# LPF_Block.net
KiCad netlist of a schematic drawn in Altium Designer
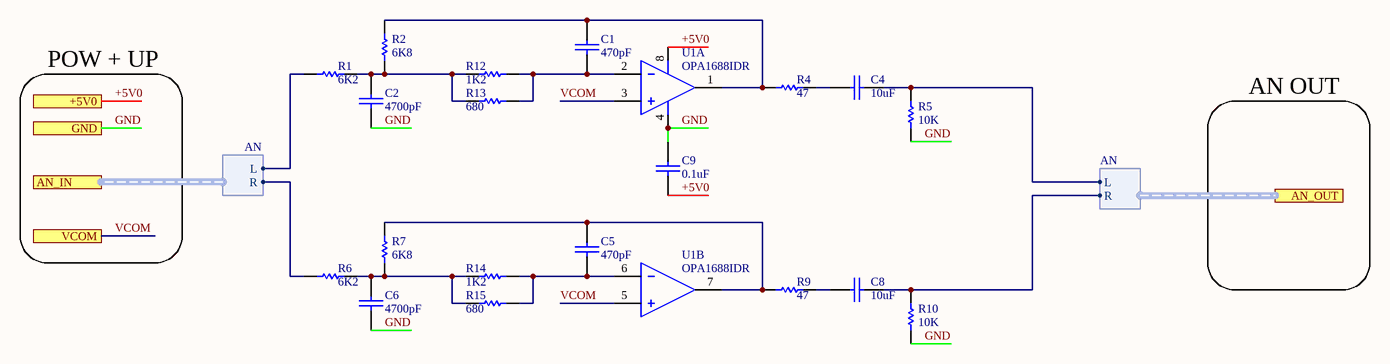
[diagram p0: LPF_Block.SchDoc]

(export (version "E")
  (design (tool "Eeschema 10.0.6"))
  (components
    (comp (ref "C1")
      (value "470pF")
      (footprint "0402-CAP-TDK")
      (fields (field (name "JLCPART") "C1537"))
      (libsource (lib "LIB2022 - Passives") (part "CAP-SMD"))
    )
    (comp (ref "C2")
      (value "4700pF")
      (footprint "0402-CAP-TDK")
      (fields (field (name "JLCPART") "C1538"))
      (libsource (lib "LIB2022 - Passives") (part "CAP-SMD"))
    )
    (comp (ref "C4")
      (value "10uF")
      (footprint "0603-CAP-TDK")
      (fields (field (name "JLCPART") "C96446"))
      (libsource (lib "LIB2022 - Passives") (part "CAP-SMD"))
    )
    (comp (ref "C5")
      (value "470pF")
      (footprint "0402-CAP-TDK")
      (fields (field (name "JLCPART") "C1537"))
      (libsource (lib "LIB2022 - Passives") (part "CAP-SMD"))
    )
    (comp (ref "C6")
      (value "4700pF")
      (footprint "0402-CAP-TDK")
      (fields (field (name "JLCPART") "C1538"))
      (libsource (lib "LIB2022 - Passives") (part "CAP-SMD"))
    )
    (comp (ref "C8")
      (value "10uF")
      (footprint "0603-CAP-TDK")
      (fields (field (name "JLCPART") "C96446"))
      (libsource (lib "LIB2022 - Passives") (part "CAP-SMD"))
    )
    (comp (ref "C9")
      (value "0.1uF")
      (footprint "0402-CAP-TDK")
      (fields (field (name "JLCPART") "C307331"))
      (libsource (lib "LIB2022 - Passives") (part "CAP-SMD"))
    )
    (comp (ref "R1")
      (value "6K2")
      (footprint "0603-RES-PANASONIC")
      (fields (field (name "JLCPART") "C4260"))
      (libsource (lib "LIB2022 - Passives") (part "RES-SMD"))
    )
    (comp (ref "R2")
      (value "6K8")
      (footprint "0402-RES-PANASONIC")
      (fields (field (name "JLCPART") "C25917"))
      (libsource (lib "LIB2022 - Passives") (part "RES-SMD"))
    )
    (comp (ref "R4")
      (value "47")
      (footprint "0402-RES-PANASONIC")
      (fields (field (name "JLCPART") "C25118"))
      (libsource (lib "LIB2022 - Passives") (part "RES-SMD"))
    )
    (comp (ref "R5")
      (value "10K")
      (footprint "0402-RES-PANASONIC")
      (fields (field (name "JLCPART") "C25744"))
      (libsource (lib "LIB2022 - Passives") (part "RES-SMD"))
    )
    (comp (ref "R6")
      (value "6K2")
      (footprint "0603-RES-PANASONIC")
      (fields (field (name "JLCPART") "C4260"))
      (libsource (lib "LIB2022 - Passives") (part "RES-SMD"))
    )
    (comp (ref "R7")
      (value "6K8")
      (footprint "0402-RES-PANASONIC")
      (fields (field (name "JLCPART") "C25917"))
      (libsource (lib "LIB2022 - Passives") (part "RES-SMD"))
    )
    (comp (ref "R9")
      (value "47")
      (footprint "0402-RES-PANASONIC")
      (fields (field (name "JLCPART") "C25118"))
      (libsource (lib "LIB2022 - Passives") (part "RES-SMD"))
    )
    (comp (ref "R10")
      (value "10K")
      (footprint "0402-RES-PANASONIC")
      (fields (field (name "JLCPART") "C25744"))
      (libsource (lib "LIB2022 - Passives") (part "RES-SMD"))
    )
    (comp (ref "R12")
      (value "1K2")
      (footprint "0402-RES-PANASONIC")
      (fields (field (name "JLCPART") "C25862"))
      (libsource (lib "LIB2022 - Passives") (part "RES-SMD"))
    )
    (comp (ref "R13")
      (value "680")
      (footprint "0402-RES-PANASONIC")
      (fields (field (name "JLCPART") "C25130"))
      (libsource (lib "LIB2022 - Passives") (part "RES-SMD"))
    )
    (comp (ref "R14")
      (value "1K2")
      (footprint "0402-RES-PANASONIC")
      (fields (field (name "JLCPART") "C25862"))
      (libsource (lib "LIB2022 - Passives") (part "RES-SMD"))
    )
    (comp (ref "R15")
      (value "680")
      (footprint "0402-RES-PANASONIC")
      (fields (field (name "JLCPART") "C25130"))
      (libsource (lib "LIB2022 - Passives") (part "RES-SMD"))
    )
    (comp (ref "U1")
      (value "OPA1688IDR")
      (footprint "TI-SOIC-8")
      (description "Rail-To-Rail Amplifier 2 Circuit - 8-SOIC")
      (fields (field (name "JLCPART") "C206212"))
      (libsource (lib "LIB2022 - ICs") (part "OPA1688IDR"))
    )
  )
  (nets
    (net (code "2") (name "/+5V0") (class "Default")
      (node (ref "C9") (pin "1") (pinfunction "1_1") (pintype "passive"))
      (node (ref "U1") (pin "8") (pinfunction "VDD_8") (pintype "power_in"))
    )
    (net (code "3") (name "/GND") (class "Default")
      (node (ref "C2") (pin "1") (pinfunction "1_1") (pintype "passive"))
      (node (ref "C6") (pin "1") (pinfunction "1_1") (pintype "passive"))
      (node (ref "C9") (pin "2") (pinfunction "2_2") (pintype "passive"))
      (node (ref "R10") (pin "1") (pinfunction "1_1") (pintype "passive"))
      (node (ref "R5") (pin "1") (pinfunction "1_1") (pintype "passive"))
      (node (ref "U1") (pin "4") (pinfunction "GND_4") (pintype "passive"))
    )
    (net (code "4") (name "/VCOM") (class "Default")
      (node (ref "U1") (pin "3") (pinfunction "1IN+_3") (pintype "passive"))
      (node (ref "U1") (pin "5") (pinfunction "2IN+_5") (pintype "passive"))
    )
    (net (code "6") (name "Net-(C2-Pad2)") (class "Default")
      (node (ref "C2") (pin "2") (pinfunction "2_2") (pintype "passive"))
      (node (ref "R1") (pin "1") (pinfunction "1_1") (pintype "passive"))
      (node (ref "R12") (pin "1") (pinfunction "1_1") (pintype "passive"))
      (node (ref "R13") (pin "1") (pinfunction "1_1") (pintype "passive"))
      (node (ref "R2") (pin "1") (pinfunction "1_1") (pintype "passive"))
    )
    (net (code "7") (name "Net-(C4-Pad1)") (class "Default")
      (node (ref "C4") (pin "1") (pinfunction "1_1") (pintype "passive"))
      (node (ref "R5") (pin "2") (pinfunction "2_2") (pintype "passive"))
    )
    (net (code "8") (name "Net-(C4-Pad2)") (class "Default")
      (node (ref "C4") (pin "2") (pinfunction "2_2") (pintype "passive"))
      (node (ref "R4") (pin "1") (pinfunction "1_1") (pintype "passive"))
    )
    (net (code "9") (name "Net-(C6-Pad2)") (class "Default")
      (node (ref "C6") (pin "2") (pinfunction "2_2") (pintype "passive"))
      (node (ref "R14") (pin "1") (pinfunction "1_1") (pintype "passive"))
      (node (ref "R15") (pin "1") (pinfunction "1_1") (pintype "passive"))
      (node (ref "R6") (pin "1") (pinfunction "1_1") (pintype "passive"))
      (node (ref "R7") (pin "1") (pinfunction "1_1") (pintype "passive"))
    )
    (net (code "10") (name "Net-(C8-Pad1)") (class "Default")
      (node (ref "C8") (pin "1") (pinfunction "1_1") (pintype "passive"))
      (node (ref "R10") (pin "2") (pinfunction "2_2") (pintype "passive"))
    )
    (net (code "11") (name "Net-(C8-Pad2)") (class "Default")
      (node (ref "C8") (pin "2") (pinfunction "2_2") (pintype "passive"))
      (node (ref "R9") (pin "1") (pinfunction "1_1") (pintype "passive"))
    )
    (net (code "12") (name "Net-(U1A-1IN-)") (class "Default")
      (node (ref "C1") (pin "1") (pinfunction "1_1") (pintype "passive"))
      (node (ref "R12") (pin "2") (pinfunction "2_2") (pintype "passive"))
      (node (ref "R13") (pin "2") (pinfunction "2_2") (pintype "passive"))
      (node (ref "U1") (pin "2") (pinfunction "1IN-_2") (pintype "passive"))
    )
    (net (code "13") (name "Net-(U1A-1OUT)") (class "Default")
      (node (ref "C1") (pin "2") (pinfunction "2_2") (pintype "passive"))
      (node (ref "R2") (pin "2") (pinfunction "2_2") (pintype "passive"))
      (node (ref "R4") (pin "2") (pinfunction "2_2") (pintype "passive"))
      (node (ref "U1") (pin "1") (pinfunction "1OUT_1") (pintype "passive"))
    )
    (net (code "14") (name "Net-(U1B-2IN-)") (class "Default")
      (node (ref "C5") (pin "1") (pinfunction "1_1") (pintype "passive"))
      (node (ref "R14") (pin "2") (pinfunction "2_2") (pintype "passive"))
      (node (ref "R15") (pin "2") (pinfunction "2_2") (pintype "passive"))
      (node (ref "U1") (pin "6") (pinfunction "2IN-_6") (pintype "passive"))
    )
    (net (code "15") (name "Net-(U1B-2OUT)") (class "Default")
      (node (ref "C5") (pin "2") (pinfunction "2_2") (pintype "passive"))
      (node (ref "R7") (pin "2") (pinfunction "2_2") (pintype "passive"))
      (node (ref "R9") (pin "2") (pinfunction "2_2") (pintype "passive"))
      (node (ref "U1") (pin "7") (pinfunction "2OUT_7") (pintype "passive"))
    )
    (net (code "16") (name "unconnected-(R1-Pad2)") (class "Default")
      (node (ref "R1") (pin "2") (pinfunction "2_2") (pintype "passive"))
    )
    (net (code "17") (name "unconnected-(R6-Pad2)") (class "Default")
      (node (ref "R6") (pin "2") (pinfunction "2_2") (pintype "passive"))
    )
  )
)
